# Channel.net
KiCad netlist of a schematic drawn in Altium Designer
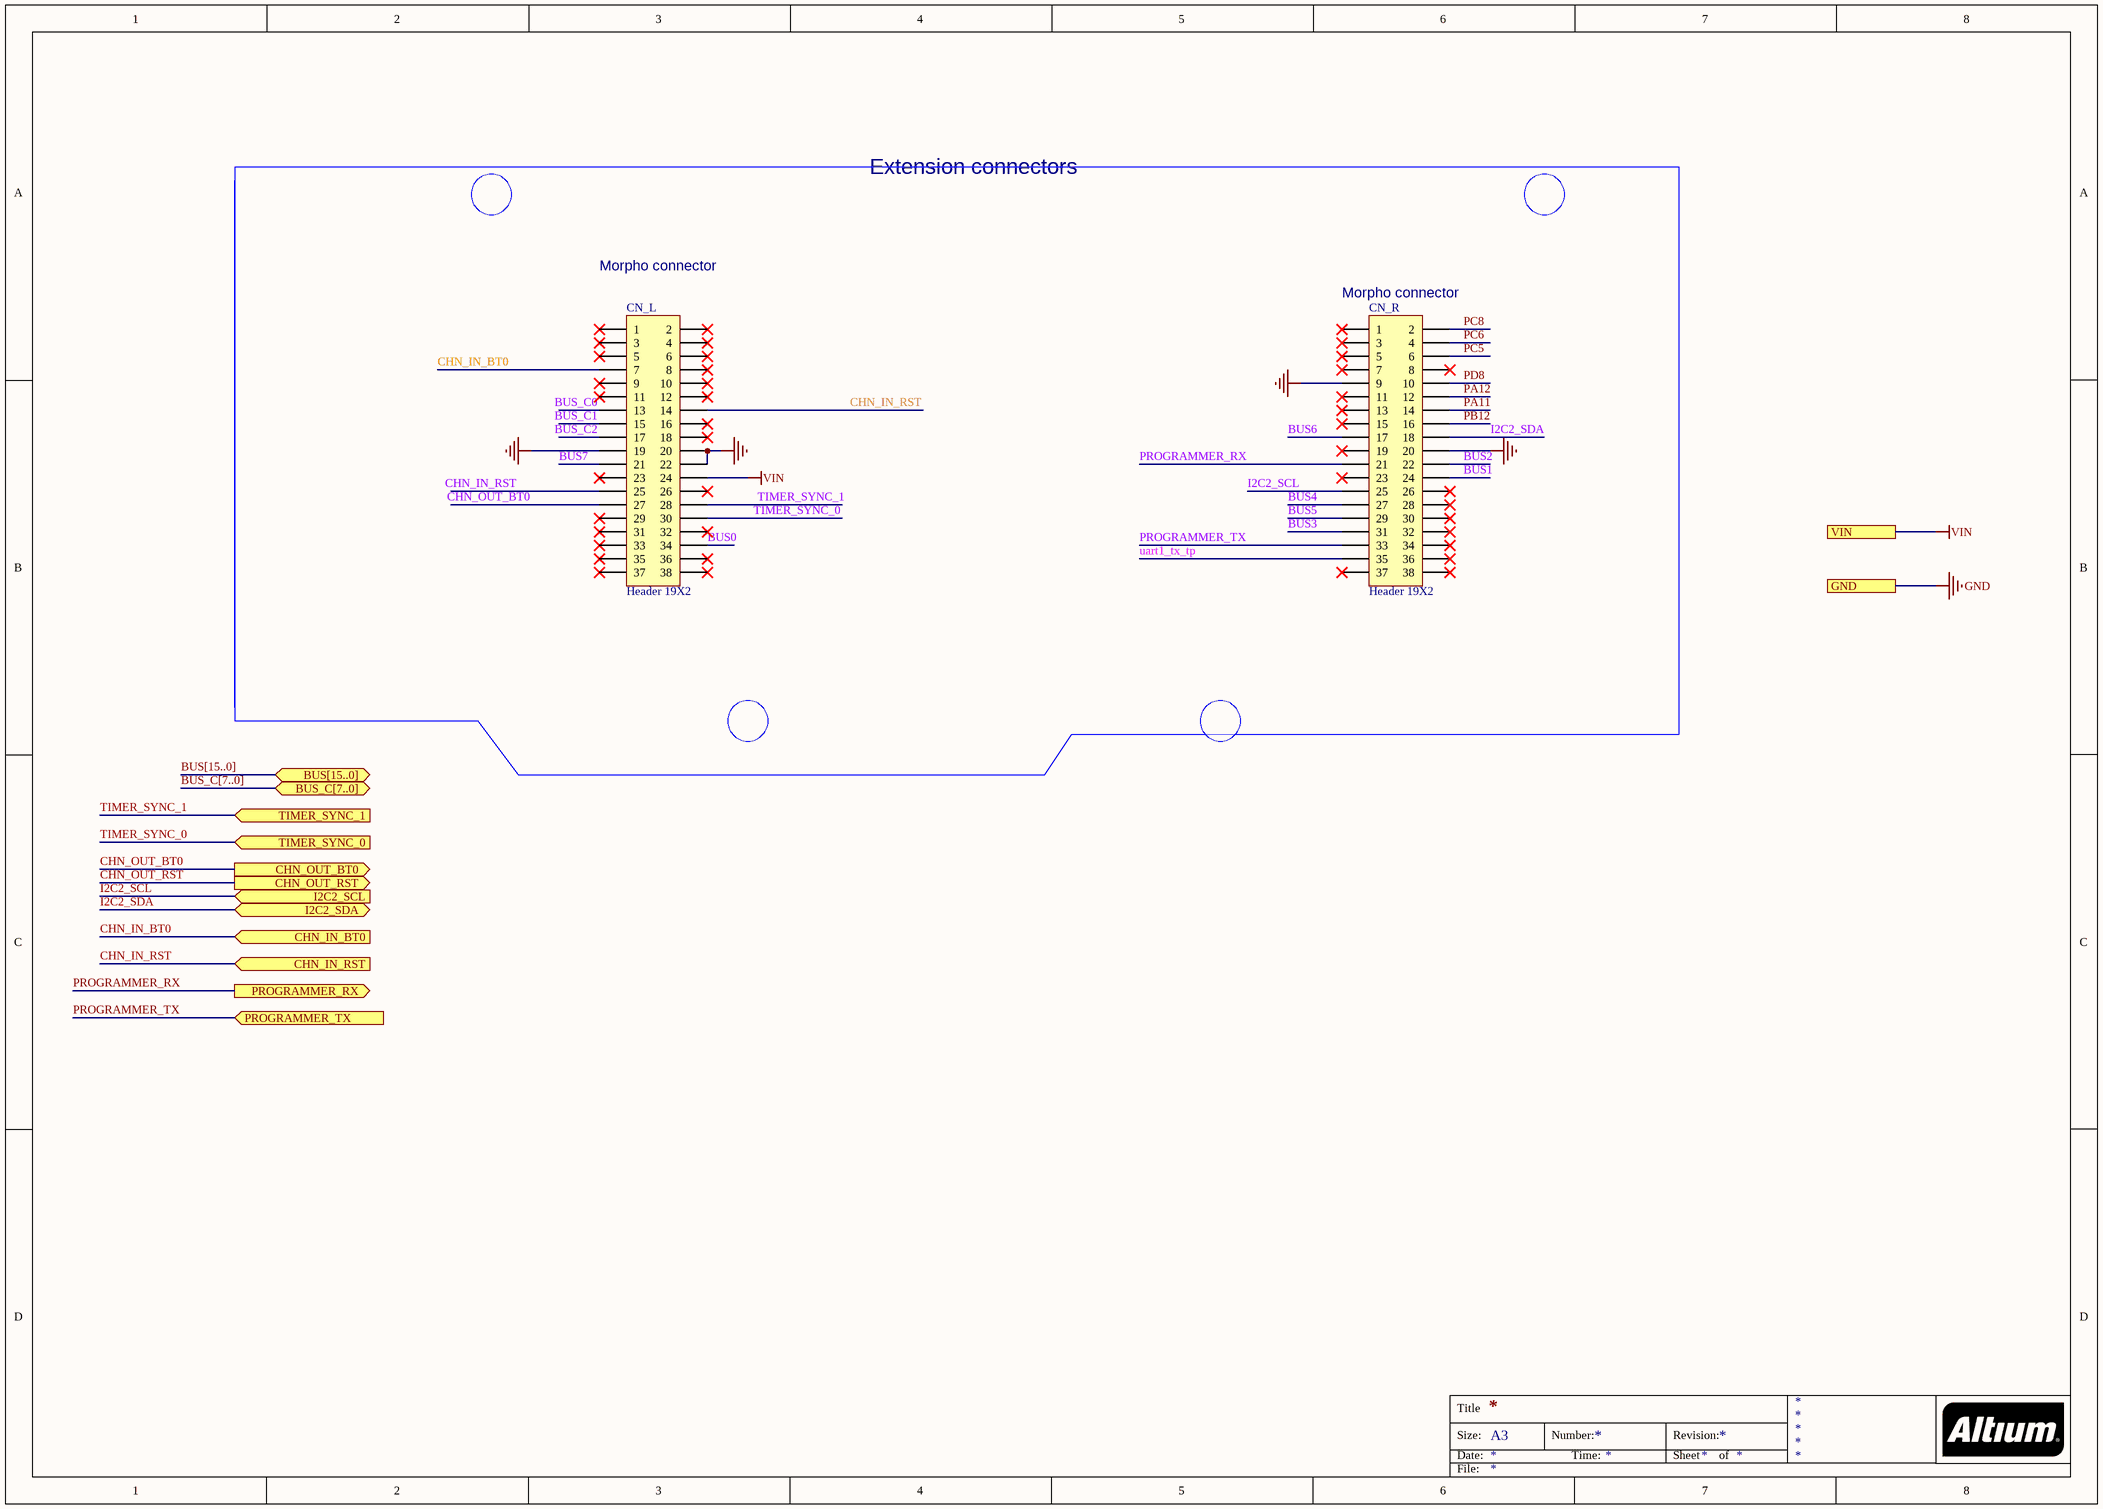
[diagram p0: Channel.SchDoc]

(export (version "E")
  (design (tool "Eeschema 10.0.6"))
  (components
    (comp (ref "CN_L")
      (value "Header 19X2")
      (footprint "HDR2X19")
      (fields (field (name "PUBLISHER") "Altium Limited"))
      (libsource (lib "Nucleo_64_1") (part "Header 19X2"))
    )
    (comp (ref "CN_R")
      (value "Header 19X2")
      (footprint "HDR2X19")
      (fields (field (name "PUBLISHER") "Altium Limited"))
      (libsource (lib "Nucleo_64_1") (part "Header 19X2"))
    )
  )
  (nets
    (net (code "14") (name "/BUS0") (class "Default")
      (node (ref "CN_L") (pin "34") (pinfunction "34_34") (pintype "passive"))
    )
    (net (code "15") (name "/BUS1") (class "Default")
      (node (ref "CN_R") (pin "24") (pinfunction "24_24") (pintype "passive"))
    )
    (net (code "16") (name "/BUS2") (class "Default")
      (node (ref "CN_R") (pin "22") (pinfunction "22_22") (pintype "passive"))
    )
    (net (code "17") (name "/BUS3") (class "Default")
      (node (ref "CN_R") (pin "31") (pinfunction "31_31") (pintype "passive"))
    )
    (net (code "18") (name "/BUS4") (class "Default")
      (node (ref "CN_R") (pin "27") (pinfunction "27_27") (pintype "passive"))
    )
    (net (code "19") (name "/BUS5") (class "Default")
      (node (ref "CN_R") (pin "29") (pinfunction "29_29") (pintype "passive"))
    )
    (net (code "20") (name "/BUS6") (class "Default")
      (node (ref "CN_R") (pin "17") (pinfunction "17_17") (pintype "passive"))
    )
    (net (code "21") (name "/BUS7") (class "Default")
      (node (ref "CN_L") (pin "21") (pinfunction "21_21") (pintype "passive"))
    )
    (net (code "23") (name "/BUS_C0") (class "Default")
      (node (ref "CN_L") (pin "13") (pinfunction "13_13") (pintype "passive"))
    )
    (net (code "24") (name "/BUS_C1") (class "Default")
      (node (ref "CN_L") (pin "15") (pinfunction "15_15") (pintype "passive"))
    )
    (net (code "25") (name "/BUS_C2") (class "Default")
      (node (ref "CN_L") (pin "17") (pinfunction "17_17") (pintype "passive"))
    )
    (net (code "27") (name "/CHN_IN_BT0") (class "Default")
      (node (ref "CN_L") (pin "7") (pinfunction "7_7") (pintype "passive"))
    )
    (net (code "28") (name "/CHN_IN_RST") (class "Default")
      (node (ref "CN_L") (pin "14") (pinfunction "14_14") (pintype "passive"))
      (node (ref "CN_L") (pin "25") (pinfunction "25_25") (pintype "passive"))
    )
    (net (code "29") (name "/CHN_OUT_BT0") (class "Default")
      (node (ref "CN_L") (pin "27") (pinfunction "27_27") (pintype "passive"))
    )
    (net (code "31") (name "/I2C2_SCL") (class "Default")
      (node (ref "CN_R") (pin "25") (pinfunction "25_25") (pintype "passive"))
    )
    (net (code "32") (name "/I2C2_SDA") (class "Default")
      (node (ref "CN_R") (pin "18") (pinfunction "18_18") (pintype "passive"))
    )
    (net (code "33") (name "/PA11") (class "Default")
      (node (ref "CN_R") (pin "14") (pinfunction "14_14") (pintype "passive"))
    )
    (net (code "34") (name "/PA12") (class "Default")
      (node (ref "CN_R") (pin "12") (pinfunction "12_12") (pintype "passive"))
    )
    (net (code "35") (name "/PB12") (class "Default")
      (node (ref "CN_R") (pin "16") (pinfunction "16_16") (pintype "passive"))
    )
    (net (code "36") (name "/PC5") (class "Default")
      (node (ref "CN_R") (pin "6") (pinfunction "6_6") (pintype "passive"))
    )
    (net (code "37") (name "/PC6") (class "Default")
      (node (ref "CN_R") (pin "4") (pinfunction "4_4") (pintype "passive"))
    )
    (net (code "38") (name "/PC8") (class "Default")
      (node (ref "CN_R") (pin "2") (pinfunction "2_2") (pintype "passive"))
    )
    (net (code "39") (name "/PD8") (class "Default")
      (node (ref "CN_R") (pin "10") (pinfunction "10_10") (pintype "passive"))
    )
    (net (code "40") (name "/PROGRAMMER_RX") (class "Default")
      (node (ref "CN_R") (pin "21") (pinfunction "21_21") (pintype "passive"))
    )
    (net (code "41") (name "/PROGRAMMER_TX") (class "Default")
      (node (ref "CN_R") (pin "33") (pinfunction "33_33") (pintype "passive"))
    )
    (net (code "42") (name "/TIMER_SYNC_0") (class "Default")
      (node (ref "CN_L") (pin "30") (pinfunction "30_30") (pintype "passive"))
    )
    (net (code "43") (name "/TIMER_SYNC_1") (class "Default")
      (node (ref "CN_L") (pin "28") (pinfunction "28_28") (pintype "passive"))
    )
    (net (code "44") (name "/uart1_tx_tp") (class "Default")
      (node (ref "CN_R") (pin "35") (pinfunction "35_35") (pintype "passive"))
    )
    (net (code "45") (name "GND") (class "Default")
      (node (ref "CN_L") (pin "19") (pinfunction "19_19") (pintype "passive"))
      (node (ref "CN_L") (pin "20") (pinfunction "20_20") (pintype "passive"))
      (node (ref "CN_L") (pin "22") (pinfunction "22_22") (pintype "passive"))
      (node (ref "CN_R") (pin "20") (pinfunction "20_20") (pintype "passive"))
      (node (ref "CN_R") (pin "9") (pinfunction "9_9") (pintype "passive"))
    )
    (net (code "46") (name "VIN") (class "Default")
      (node (ref "CN_L") (pin "24") (pinfunction "24_24") (pintype "passive"))
    )
    (net (code "47") (name "unconnected-(CN_L-Pad1)") (class "Default")
      (node (ref "CN_L") (pin "1") (pinfunction "1_1") (pintype "passive+no_connect"))
    )
    (net (code "48") (name "unconnected-(CN_L-Pad2)") (class "Default")
      (node (ref "CN_L") (pin "2") (pinfunction "2_2") (pintype "passive+no_connect"))
    )
    (net (code "49") (name "unconnected-(CN_L-Pad3)") (class "Default")
      (node (ref "CN_L") (pin "3") (pinfunction "3_3") (pintype "passive+no_connect"))
    )
    (net (code "50") (name "unconnected-(CN_L-Pad4)") (class "Default")
      (node (ref "CN_L") (pin "4") (pinfunction "4_4") (pintype "passive+no_connect"))
    )
    (net (code "51") (name "unconnected-(CN_L-Pad5)") (class "Default")
      (node (ref "CN_L") (pin "5") (pinfunction "5_5") (pintype "passive+no_connect"))
    )
    (net (code "52") (name "unconnected-(CN_L-Pad6)") (class "Default")
      (node (ref "CN_L") (pin "6") (pinfunction "6_6") (pintype "passive+no_connect"))
    )
    (net (code "53") (name "unconnected-(CN_L-Pad8)") (class "Default")
      (node (ref "CN_L") (pin "8") (pinfunction "8_8") (pintype "passive+no_connect"))
    )
    (net (code "54") (name "unconnected-(CN_L-Pad9)") (class "Default")
      (node (ref "CN_L") (pin "9") (pinfunction "9_9") (pintype "passive+no_connect"))
    )
    (net (code "55") (name "unconnected-(CN_L-Pad10)") (class "Default")
      (node (ref "CN_L") (pin "10") (pinfunction "10_10") (pintype "passive+no_connect"))
    )
    (net (code "56") (name "unconnected-(CN_L-Pad11)") (class "Default")
      (node (ref "CN_L") (pin "11") (pinfunction "11_11") (pintype "passive+no_connect"))
    )
    (net (code "57") (name "unconnected-(CN_L-Pad12)") (class "Default")
      (node (ref "CN_L") (pin "12") (pinfunction "12_12") (pintype "passive+no_connect"))
    )
    (net (code "58") (name "unconnected-(CN_L-Pad16)") (class "Default")
      (node (ref "CN_L") (pin "16") (pinfunction "16_16") (pintype "passive+no_connect"))
    )
    (net (code "59") (name "unconnected-(CN_L-Pad18)") (class "Default")
      (node (ref "CN_L") (pin "18") (pinfunction "18_18") (pintype "passive+no_connect"))
    )
    (net (code "60") (name "unconnected-(CN_L-Pad23)") (class "Default")
      (node (ref "CN_L") (pin "23") (pinfunction "23_23") (pintype "passive+no_connect"))
    )
    (net (code "61") (name "unconnected-(CN_L-Pad26)") (class "Default")
      (node (ref "CN_L") (pin "26") (pinfunction "26_26") (pintype "passive+no_connect"))
    )
    (net (code "62") (name "unconnected-(CN_L-Pad29)") (class "Default")
      (node (ref "CN_L") (pin "29") (pinfunction "29_29") (pintype "passive+no_connect"))
    )
    (net (code "63") (name "unconnected-(CN_L-Pad31)") (class "Default")
      (node (ref "CN_L") (pin "31") (pinfunction "31_31") (pintype "passive+no_connect"))
    )
    (net (code "64") (name "unconnected-(CN_L-Pad32)") (class "Default")
      (node (ref "CN_L") (pin "32") (pinfunction "32_32") (pintype "passive+no_connect"))
    )
    (net (code "65") (name "unconnected-(CN_L-Pad33)") (class "Default")
      (node (ref "CN_L") (pin "33") (pinfunction "33_33") (pintype "passive+no_connect"))
    )
    (net (code "66") (name "unconnected-(CN_L-Pad35)") (class "Default")
      (node (ref "CN_L") (pin "35") (pinfunction "35_35") (pintype "passive+no_connect"))
    )
    (net (code "67") (name "unconnected-(CN_L-Pad36)") (class "Default")
      (node (ref "CN_L") (pin "36") (pinfunction "36_36") (pintype "passive+no_connect"))
    )
    (net (code "68") (name "unconnected-(CN_L-Pad37)") (class "Default")
      (node (ref "CN_L") (pin "37") (pinfunction "37_37") (pintype "passive+no_connect"))
    )
    (net (code "69") (name "unconnected-(CN_L-Pad38)") (class "Default")
      (node (ref "CN_L") (pin "38") (pinfunction "38_38") (pintype "passive+no_connect"))
    )
    (net (code "70") (name "unconnected-(CN_R-Pad1)") (class "Default")
      (node (ref "CN_R") (pin "1") (pinfunction "1_1") (pintype "passive+no_connect"))
    )
    (net (code "71") (name "unconnected-(CN_R-Pad3)") (class "Default")
      (node (ref "CN_R") (pin "3") (pinfunction "3_3") (pintype "passive+no_connect"))
    )
    (net (code "72") (name "unconnected-(CN_R-Pad5)") (class "Default")
      (node (ref "CN_R") (pin "5") (pinfunction "5_5") (pintype "passive+no_connect"))
    )
    (net (code "73") (name "unconnected-(CN_R-Pad7)") (class "Default")
      (node (ref "CN_R") (pin "7") (pinfunction "7_7") (pintype "passive+no_connect"))
    )
    (net (code "74") (name "unconnected-(CN_R-Pad8)") (class "Default")
      (node (ref "CN_R") (pin "8") (pinfunction "8_8") (pintype "passive+no_connect"))
    )
    (net (code "75") (name "unconnected-(CN_R-Pad11)") (class "Default")
      (node (ref "CN_R") (pin "11") (pinfunction "11_11") (pintype "passive+no_connect"))
    )
    (net (code "76") (name "unconnected-(CN_R-Pad13)") (class "Default")
      (node (ref "CN_R") (pin "13") (pinfunction "13_13") (pintype "passive+no_connect"))
    )
    (net (code "77") (name "unconnected-(CN_R-Pad15)") (class "Default")
      (node (ref "CN_R") (pin "15") (pinfunction "15_15") (pintype "passive+no_connect"))
    )
    (net (code "78") (name "unconnected-(CN_R-Pad19)") (class "Default")
      (node (ref "CN_R") (pin "19") (pinfunction "19_19") (pintype "passive+no_connect"))
    )
    (net (code "79") (name "unconnected-(CN_R-Pad23)") (class "Default")
      (node (ref "CN_R") (pin "23") (pinfunction "23_23") (pintype "passive+no_connect"))
    )
    (net (code "80") (name "unconnected-(CN_R-Pad26)") (class "Default")
      (node (ref "CN_R") (pin "26") (pinfunction "26_26") (pintype "passive+no_connect"))
    )
    (net (code "81") (name "unconnected-(CN_R-Pad28)") (class "Default")
      (node (ref "CN_R") (pin "28") (pinfunction "28_28") (pintype "passive+no_connect"))
    )
    (net (code "82") (name "unconnected-(CN_R-Pad30)") (class "Default")
      (node (ref "CN_R") (pin "30") (pinfunction "30_30") (pintype "passive+no_connect"))
    )
    (net (code "83") (name "unconnected-(CN_R-Pad32)") (class "Default")
      (node (ref "CN_R") (pin "32") (pinfunction "32_32") (pintype "passive+no_connect"))
    )
    (net (code "84") (name "unconnected-(CN_R-Pad34)") (class "Default")
      (node (ref "CN_R") (pin "34") (pinfunction "34_34") (pintype "passive+no_connect"))
    )
    (net (code "85") (name "unconnected-(CN_R-Pad36)") (class "Default")
      (node (ref "CN_R") (pin "36") (pinfunction "36_36") (pintype "passive+no_connect"))
    )
    (net (code "86") (name "unconnected-(CN_R-Pad37)") (class "Default")
      (node (ref "CN_R") (pin "37") (pinfunction "37_37") (pintype "passive+no_connect"))
    )
    (net (code "87") (name "unconnected-(CN_R-Pad38)") (class "Default")
      (node (ref "CN_R") (pin "38") (pinfunction "38_38") (pintype "passive+no_connect"))
    )
  )
)
